# T_module.net
KiCad netlist of a schematic drawn in Altium Designer
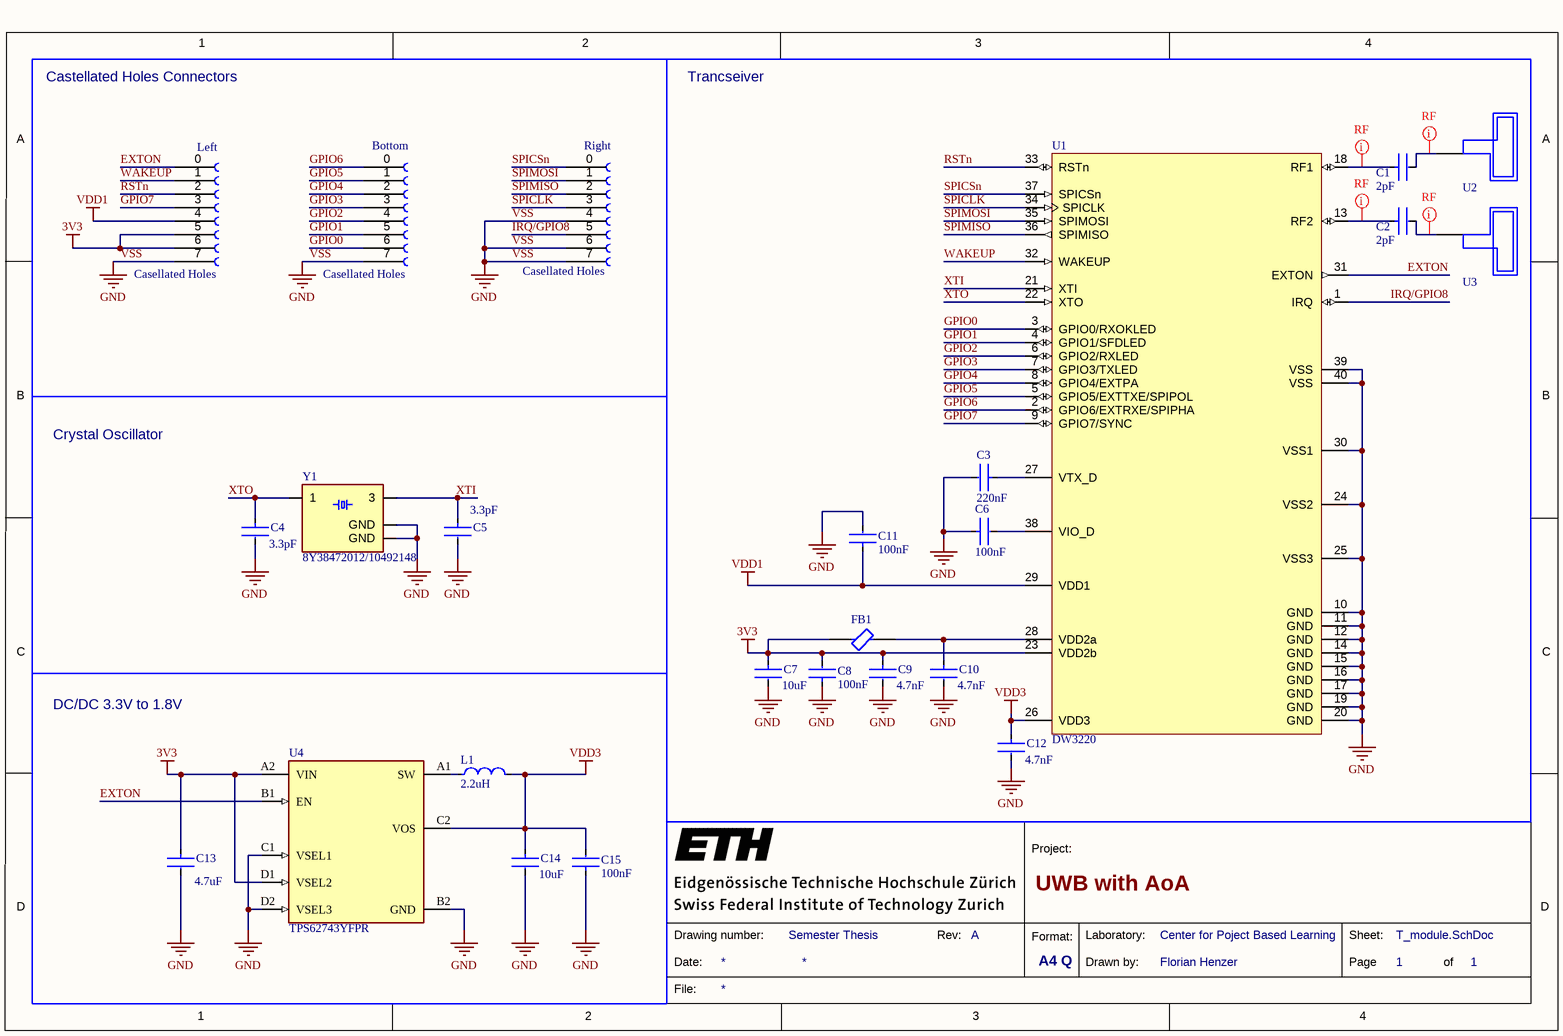
[diagram p0: T_module.SchDoc]

(export (version "E")
  (design (tool "Eeschema 10.0.6"))
  (components
    (comp (ref "Bottom")
      (value "Casellated Holes")
      (footprint "PcbLib1:8 Castelted holes")
      (libsource (lib "Schlib1") (part "Casellated Holes"))
    )
    (comp (ref "C1")
      (value "GJM0335C1E2R0WB01D")
      (footprint "FP-GJM033-0_03-IPC_B")
      (description "Ceramic Capacitor 2pF ±0.05pF 25V C0G 0201 (0603 Metric)")
      (fields (field (name "CAPACITANCE") "2pF"))
      (libsource (lib "Altium Content Vault") (part "b4654b650e69147ec39a6b967a45e02"))
    )
    (comp (ref "C2")
      (value "GJM0335C1E2R0WB01D")
      (footprint "FP-GJM033-0_03-IPC_B")
      (description "Ceramic Capacitor 2pF ±0.05pF 25V C0G 0201 (0603 Metric)")
      (fields (field (name "CAPACITANCE") "2pF"))
      (libsource (lib "Altium Content Vault") (part "b4654b650e69147ec39a6b967a45e02"))
    )
    (comp (ref "C3")
      (value "CL03A224KQ3NNNC")
      (footprint "FP-CL03-IPC_B")
      (description "Cap Ceramic 220nF 6.3V X5R ±10% Pad SMD 0201 +85°C T/R")
      (fields (field (name "CAPACITANCE") "220nF") (field (name "TOLERANCE") "10%"))
      (libsource (lib "Altium Content Vault") (part "b4654b650e69147ec39a6b967a45e02"))
    )
    (comp (ref "C4")
      (value "GRM0335C1H3R3CA01D")
      (footprint "FP-GRM033-0_03-IPC_A")
      (description "Chip Multilayer Ceramic Capacitors for General Purpose, 0201, 3.3pF, C0G, 30ppm/°C, 0.25pF, 50V")
      (fields (field (name "CAPACITANCE") "3.3pF"))
      (libsource (lib "Altium Content Vault") (part "b4654b650e69147ec39a6b967a45e02"))
    )
    (comp (ref "C5")
      (value "GRM0335C1H3R3CA01D")
      (footprint "FP-GRM033-0_03-IPC_A")
      (description "Chip Multilayer Ceramic Capacitors for General Purpose, 0201, 3.3pF, C0G, 30ppm/°C, 0.25pF, 50V")
      (fields (field (name "CAPACITANCE") "3.3pF"))
      (libsource (lib "Altium Content Vault") (part "b4654b650e69147ec39a6b967a45e02"))
    )
    (comp (ref "C6")
      (value "CL03A104KQ3NNNH")
      (footprint "FP-CL03-IPC_B")
      (description "Cap Ceramic 100nF 6.3V X5R ±10% Pad SMD 0201 +85°C T/R")
      (fields (field (name "TOLERANCE") "10%") (field (name "CAPACITANCE") "100nF"))
      (libsource (lib "Altium Content Vault") (part "b4654b650e69147ec39a6b967a45e02"))
    )
    (comp (ref "C7")
      (value "GRM155R60J106ME47D")
      (footprint "FP-GRM155-0_2-0_1-IPC_B")
      (description "Chip Multilayer Ceramic Capacitors for General Purpose, 0402, 10uF, X5R, 15%, 20%, 6.3V")
      (fields (field (name "TOLERANCE") "20%") (field (name "CAPACITANCE") "10uF"))
      (libsource (lib "Altium Content Vault") (part "b4654b650e69147ec39a6b967a45e02"))
    )
    (comp (ref "C8")
      (value "CL03A104KQ3NNNH")
      (footprint "FP-CL03-IPC_B")
      (description "Cap Ceramic 100nF 6.3V X5R ±10% Pad SMD 0201 +85°C T/R")
      (fields (field (name "TOLERANCE") "10%") (field (name "CAPACITANCE") "100nF"))
      (libsource (lib "Altium Content Vault") (part "b4654b650e69147ec39a6b967a45e02"))
    )
    (comp (ref "C9")
      (value "GRM033R71A472KA01D")
      (footprint "FP-GRM033-0_03-IPC_A")
      (description "Chip Multilayer Ceramic Capacitors for General Purpose, 0201, 4700pF, X7R, 15%, 10%, 10V")
      (fields
        (field (name "VOLTAGE") "10V")
        (field (name "CAPACITANCE") "4.7nF")
        (field (name "TOLERANCE") "10%")
      )
      (libsource (lib "Altium Content Vault") (part "b4654b650e69147ec39a6b967a45e02"))
    )
    (comp (ref "C10")
      (value "GRM033R71A472KA01D")
      (footprint "FP-GRM033-0_03-IPC_A")
      (description "Chip Multilayer Ceramic Capacitors for General Purpose, 0201, 4700pF, X7R, 15%, 10%, 10V")
      (fields
        (field (name "VOLTAGE") "10V")
        (field (name "CAPACITANCE") "4.7nF")
        (field (name "TOLERANCE") "10%")
      )
      (libsource (lib "Altium Content Vault") (part "b4654b650e69147ec39a6b967a45e02"))
    )
    (comp (ref "C11")
      (value "CL03A104KQ3NNNH")
      (footprint "FP-CL03-IPC_B")
      (description "Cap Ceramic 100nF 6.3V X5R ±10% Pad SMD 0201 +85°C T/R")
      (fields (field (name "TOLERANCE") "10%") (field (name "CAPACITANCE") "100nF"))
      (libsource (lib "Altium Content Vault") (part "b4654b650e69147ec39a6b967a45e02"))
    )
    (comp (ref "C12")
      (value "GRM033R71A472KA01D")
      (footprint "FP-GRM033-0_03-IPC_A")
      (description "Chip Multilayer Ceramic Capacitors for General Purpose, 0201, 4700pF, X7R, 15%, 10%, 10V")
      (fields
        (field (name "VOLTAGE") "10V")
        (field (name "CAPACITANCE") "4.7nF")
        (field (name "TOLERANCE") "10%")
      )
      (libsource (lib "Altium Content Vault") (part "b4654b650e69147ec39a6b967a45e02"))
    )
    (comp (ref "C13")
      (value "GRM035R60J475ME15D")
      (footprint "FP-GRM035-0_09-IPC_B")
      (description "Chip Multilayer Ceramic Capacitors for General Purpose, 0201, 4.7uF, X5R, 15%, 20%, 6.3V")
      (fields (field (name "CAPACITANCE") "4.7uF") (field (name "TOLERANCE") "20%"))
      (libsource (lib "Altium Content Vault") (part "02cd4be3c70576c341d710602a673aa"))
    )
    (comp (ref "C14")
      (value "GRM155R60J106ME47D")
      (footprint "FP-GRM155-0_2-0_1-IPC_C")
      (description "Chip Multilayer Ceramic Capacitors for General Purpose, 0402, 10uF, X5R, 15%, 20%, 6.3V")
      (fields (field (name "TOLERANCE") "20%") (field (name "CAPACITANCE") "10uF"))
      (libsource (lib "Altium Content Vault") (part "b4654b650e69147ec39a6b967a45e02"))
    )
    (comp (ref "C15")
      (value "CL03A104KQ3NNNH")
      (footprint "FP-CL03-IPC_B")
      (description "Cap Ceramic 100nF 6.3V X5R ±10% Pad SMD 0201 +85°C T/R")
      (fields (field (name "TOLERANCE") "10%") (field (name "CAPACITANCE") "100nF"))
      (libsource (lib "Altium Content Vault") (part "b4654b650e69147ec39a6b967a45e02"))
    )
    (comp (ref "FB1")
      (value "MPZ0603S330HT000")
      (footprint "FP-MPZ0603-IPC_B")
      (description "CHIP BEADS FOR GENERAL SIGNAL LI")
      (libsource (lib "Altium Content Vault") (part "5f30dd21d616792df468990f7003faa"))
    )
    (comp (ref "L1")
      (value "1285AS-H-2R2M=P2")
      (footprint "FP-DFE201610C-IPC_C")
      (description "Shielded Wirewound Inductor 2.2uH 20% 1200mA 0.204Ω 0806 (2016)")
      (fields (field (name "INDUCTANCE") "2.2uH") (field (name "TOLERANCE") "20%"))
      (libsource (lib "Altium Content Vault") (part "725321dda6339637d4d059423bc1c3c"))
    )
    (comp (ref "Left")
      (value "Casellated Holes")
      (footprint "PcbLib1:8 Castelted holes")
      (libsource (lib "Schlib1") (part "Casellated Holes"))
    )
    (comp (ref "Right")
      (value "Casellated Holes")
      (footprint "PcbLib1:8 Castelted holes")
      (libsource (lib "Schlib1") (part "Casellated Holes"))
    )
    (comp (ref "U1")
      (value "DW3220")
      (footprint "QFN40P500X500X40_HS-40N")
      (description "Ultra-low power Wi-Fi 802.11b/g/n, without mounted antenna")
      (fields (field (name "MANUFACTURER") "Qorvo"))
      (libsource (lib "ETHZ Vault") (part "DW3220"))
    )
    (comp (ref "U2")
      (value "AH086M555003-T")
      (footprint "AH086M")
      (description "3.5GHz, 5.6GHz WiMax™ Chip RF Antenna 3.1GHz ~ 8GHz 2.6dBi, 0.7dBi Solder Surface Mount")
      (libsource (lib "ETHZ Vault") (part "Antenna"))
    )
    (comp (ref "U3")
      (value "AH086M555003-T")
      (footprint "AH086M")
      (description "3.5GHz, 5.6GHz WiMax™ Chip RF Antenna 3.1GHz ~ 8GHz 2.6dBi, 0.7dBi Solder Surface Mount")
      (libsource (lib "ETHZ Vault") (part "Antenna"))
    )
    (comp (ref "U4")
      (value "TPS62743YFPR")
      (footprint "FP-YFP0008-C01-MFG")
      (description "IC REG BUCK PROG 300MA 8DSBGA")
      (libsource (lib "Altium Content Vault") (part "8afa53303d55f9e28cdff5b5725789a"))
    )
    (comp (ref "Y1")
      (value "8Y38472012/10492148")
      (footprint "OSCSC320X250X100N - small Footprint")
      (description "https://www.digikey.ch/de/products/detail/txc-corporation/8Y38472012/10492148")
      (libsource (lib "ABM8G-14.31818MHZ-B4Y-T") (part "ABM8G-14.31818MHZ-B4Y-T"))
    )
  )
  (nets
    (net (code "1") (name "/EXTON") (class "Default")
      (node (ref "Left") (pin "0") (pinfunction "0_0") (pintype "passive"))
      (node (ref "U1") (pin "31") (pinfunction "EXTON_31") (pintype "output"))
      (node (ref "U4") (pin "B1") (pinfunction "EN_B1") (pintype "input"))
    )
    (net (code "2") (name "/GPIO0") (class "Default")
      (node (ref "Bottom") (pin "6") (pinfunction "0_6") (pintype "passive"))
      (node (ref "U1") (pin "3") (pinfunction "GPIO0/RXOKLED_3") (pintype "bidirectional"))
    )
    (net (code "3") (name "/GPIO1") (class "Default")
      (node (ref "Bottom") (pin "5") (pinfunction "0_5") (pintype "passive"))
      (node (ref "U1") (pin "4") (pinfunction "GPIO1/SFDLED_4") (pintype "bidirectional"))
    )
    (net (code "4") (name "/GPIO2") (class "Default")
      (node (ref "Bottom") (pin "4") (pinfunction "0_4") (pintype "passive"))
      (node (ref "U1") (pin "6") (pinfunction "GPIO2/RXLED_6") (pintype "bidirectional"))
    )
    (net (code "5") (name "/GPIO3") (class "Default")
      (node (ref "Bottom") (pin "3") (pinfunction "0_3") (pintype "passive"))
      (node (ref "U1") (pin "7") (pinfunction "GPIO3/TXLED_7") (pintype "bidirectional"))
    )
    (net (code "6") (name "/GPIO4") (class "Default")
      (node (ref "Bottom") (pin "2") (pinfunction "0_2") (pintype "passive"))
      (node (ref "U1") (pin "8") (pinfunction "GPIO4/EXTPA_8") (pintype "bidirectional"))
    )
    (net (code "7") (name "/GPIO5") (class "Default")
      (node (ref "Bottom") (pin "1") (pinfunction "0_1") (pintype "passive"))
      (node (ref "U1") (pin "5") (pinfunction "GPIO5/EXTTXE/SPIPOL_5") (pintype "bidirectional"))
    )
    (net (code "8") (name "/GPIO6") (class "Default")
      (node (ref "Bottom") (pin "0") (pinfunction "0_0") (pintype "passive"))
      (node (ref "U1") (pin "2") (pinfunction "GPIO6/EXTRXE/SPIPHA_2") (pintype "bidirectional"))
    )
    (net (code "9") (name "/GPIO7") (class "Default")
      (node (ref "Left") (pin "3") (pinfunction "0_3") (pintype "passive"))
      (node (ref "U1") (pin "9") (pinfunction "GPIO7/SYNC_9") (pintype "bidirectional"))
    )
    (net (code "10") (name "/IRQ{slash}GPIO8") (class "Default")
      (node (ref "Right") (pin "5") (pinfunction "0_5") (pintype "passive"))
      (node (ref "U1") (pin "1") (pinfunction "IRQ_1") (pintype "bidirectional"))
    )
    (net (code "11") (name "/RSTn") (class "Default")
      (node (ref "Left") (pin "2") (pinfunction "0_2") (pintype "passive"))
      (node (ref "U1") (pin "33") (pinfunction "RSTn_33") (pintype "bidirectional"))
    )
    (net (code "12") (name "/SPICLK") (class "Default")
      (node (ref "Right") (pin "3") (pinfunction "0_3") (pintype "passive"))
      (node (ref "U1") (pin "34") (pinfunction "SPICLK_34") (pintype "input"))
    )
    (net (code "13") (name "/SPICSn") (class "Default")
      (node (ref "Right") (pin "0") (pinfunction "0_0") (pintype "passive"))
      (node (ref "U1") (pin "37") (pinfunction "SPICSn_37") (pintype "input"))
    )
    (net (code "14") (name "/SPIMISO") (class "Default")
      (node (ref "Right") (pin "2") (pinfunction "0_2") (pintype "passive"))
      (node (ref "U1") (pin "36") (pinfunction "SPIMISO_36") (pintype "output"))
    )
    (net (code "15") (name "/SPIMOSI") (class "Default")
      (node (ref "Right") (pin "1") (pinfunction "0_1") (pintype "passive"))
      (node (ref "U1") (pin "35") (pinfunction "SPIMOSI_35") (pintype "input"))
    )
    (net (code "16") (name "/WAKEUP") (class "Default")
      (node (ref "Left") (pin "1") (pinfunction "0_1") (pintype "passive"))
      (node (ref "U1") (pin "32") (pinfunction "WAKEUP_32") (pintype "input"))
    )
    (net (code "17") (name "/XTI") (class "Default")
      (node (ref "C5") (pin "1") (pinfunction "1_1") (pintype "passive"))
      (node (ref "U1") (pin "21") (pinfunction "XTI_21") (pintype "input"))
      (node (ref "Y1") (pin "3") (pinfunction "3_3") (pintype "passive"))
    )
    (net (code "18") (name "/XTO") (class "Default")
      (node (ref "C4") (pin "1") (pinfunction "1_1") (pintype "passive"))
      (node (ref "U1") (pin "22") (pinfunction "XTO_22") (pintype "input"))
      (node (ref "Y1") (pin "1") (pinfunction "1_1") (pintype "passive"))
    )
    (net (code "19") (name "3V3") (class "Default")
      (node (ref "C13") (pin "1") (pinfunction "1_1") (pintype "passive"))
      (node (ref "C7") (pin "1") (pinfunction "1_1") (pintype "passive"))
      (node (ref "C8") (pin "2") (pinfunction "2_2") (pintype "passive"))
      (node (ref "C9") (pin "1") (pinfunction "1_1") (pintype "passive"))
      (node (ref "FB1") (pin "1") (pinfunction "1_1") (pintype "passive"))
      (node (ref "Left") (pin "5") (pinfunction "0_5") (pintype "passive"))
      (node (ref "Left") (pin "6") (pinfunction "0_6") (pintype "passive"))
      (node (ref "U1") (pin "23") (pinfunction "VDD2b_23") (pintype "power_in"))
      (node (ref "U4") (pin "A2") (pinfunction "VIN_A2") (pintype "power_in"))
      (node (ref "U4") (pin "D1") (pinfunction "VSEL2_D1") (pintype "input"))
    )
    (net (code "20") (name "GND") (class "Default")
      (node (ref "Bottom") (pin "7") (pinfunction "0_7") (pintype "passive"))
      (node (ref "C10") (pin "2") (pinfunction "2_2") (pintype "passive"))
      (node (ref "C11") (pin "2") (pinfunction "2_2") (pintype "passive"))
      (node (ref "C12") (pin "2") (pinfunction "2_2") (pintype "passive"))
      (node (ref "C13") (pin "2") (pinfunction "2_2") (pintype "passive"))
      (node (ref "C14") (pin "2") (pinfunction "2_2") (pintype "passive"))
      (node (ref "C15") (pin "1") (pinfunction "1_1") (pintype "passive"))
      (node (ref "C3") (pin "2") (pinfunction "2_2") (pintype "passive"))
      (node (ref "C4") (pin "2") (pinfunction "2_2") (pintype "passive"))
      (node (ref "C5") (pin "2") (pinfunction "2_2") (pintype "passive"))
      (node (ref "C6") (pin "1") (pinfunction "1_1") (pintype "passive"))
      (node (ref "C7") (pin "2") (pinfunction "2_2") (pintype "passive"))
      (node (ref "C8") (pin "1") (pinfunction "1_1") (pintype "passive"))
      (node (ref "C9") (pin "2") (pinfunction "2_2") (pintype "passive"))
      (node (ref "Left") (pin "7") (pinfunction "0_7") (pintype "passive"))
      (node (ref "Right") (pin "4") (pinfunction "0_4") (pintype "passive"))
      (node (ref "Right") (pin "6") (pinfunction "0_6") (pintype "passive"))
      (node (ref "Right") (pin "7") (pinfunction "0_7") (pintype "passive"))
      (node (ref "U1") (pin "10") (pinfunction "GND_10") (pintype "power_in"))
      (node (ref "U1") (pin "11") (pinfunction "GND_11") (pintype "power_in"))
      (node (ref "U1") (pin "12") (pinfunction "GND_12") (pintype "power_in"))
      (node (ref "U1") (pin "14") (pinfunction "GND_14") (pintype "power_in"))
      (node (ref "U1") (pin "15") (pinfunction "GND_15") (pintype "power_in"))
      (node (ref "U1") (pin "16") (pinfunction "GND_16") (pintype "power_in"))
      (node (ref "U1") (pin "17") (pinfunction "GND_17") (pintype "power_in"))
      (node (ref "U1") (pin "19") (pinfunction "GND_19") (pintype "power_in"))
      (node (ref "U1") (pin "20") (pinfunction "GND_20") (pintype "power_in"))
      (node (ref "U1") (pin "24") (pinfunction "VSS2_24") (pintype "power_in"))
      (node (ref "U1") (pin "25") (pinfunction "VSS3_25") (pintype "power_in"))
      (node (ref "U1") (pin "30") (pinfunction "VSS1_30") (pintype "power_in"))
      (node (ref "U1") (pin "39") (pinfunction "VSS_39") (pintype "power_in"))
      (node (ref "U1") (pin "40") (pinfunction "VSS_40") (pintype "power_in"))
      (node (ref "U4") (pin "B2") (pinfunction "GND_B2") (pintype "power_in"))
      (node (ref "U4") (pin "C1") (pinfunction "VSEL1_C1") (pintype "input"))
      (node (ref "U4") (pin "D2") (pinfunction "VSEL3_D2") (pintype "input"))
      (node (ref "Y1") (pin "2") (pinfunction "GND_2") (pintype "power_in"))
      (node (ref "Y1") (pin "4") (pinfunction "GND_4") (pintype "power_in"))
    )
    (net (code "21") (name "Net-(C1-Pad2)") (class "Default")
      (node (ref "C1") (pin "2") (pinfunction "2_2") (pintype "passive"))
      (node (ref "U2") (pin "1") (pinfunction "1_1") (pintype "passive"))
    )
    (net (code "22") (name "Net-(C2-Pad2)") (class "Default")
      (node (ref "C2") (pin "2") (pinfunction "2_2") (pintype "passive"))
      (node (ref "U3") (pin "1") (pinfunction "1_1") (pintype "passive"))
    )
    (net (code "23") (name "Net-(U1-RF1)") (class "Default")
      (node (ref "C1") (pin "1") (pinfunction "1_1") (pintype "passive"))
      (node (ref "U1") (pin "18") (pinfunction "RF1_18") (pintype "bidirectional"))
    )
    (net (code "24") (name "Net-(U1-RF2)") (class "Default")
      (node (ref "C2") (pin "1") (pinfunction "1_1") (pintype "passive"))
      (node (ref "U1") (pin "13") (pinfunction "RF2_13") (pintype "bidirectional"))
    )
    (net (code "25") (name "Net-(U1-VDD2a)") (class "Default")
      (node (ref "C10") (pin "1") (pinfunction "1_1") (pintype "passive"))
      (node (ref "FB1") (pin "2") (pinfunction "2_2") (pintype "passive"))
      (node (ref "U1") (pin "28") (pinfunction "VDD2a_28") (pintype "power_in"))
    )
    (net (code "26") (name "Net-(U1-VIO_D)") (class "Default")
      (node (ref "C6") (pin "2") (pinfunction "2_2") (pintype "passive"))
      (node (ref "U1") (pin "38") (pinfunction "VIO_D_38") (pintype "passive"))
    )
    (net (code "27") (name "Net-(U1-VTX_D)") (class "Default")
      (node (ref "C3") (pin "1") (pinfunction "1_1") (pintype "passive"))
      (node (ref "U1") (pin "27") (pinfunction "VTX_D_27") (pintype "passive"))
    )
    (net (code "28") (name "Net-(U4-SW)") (class "Default")
      (node (ref "L1") (pin "1") (pinfunction "1_1") (pintype "passive"))
      (node (ref "U4") (pin "A1") (pinfunction "SW_A1") (pintype "passive"))
    )
    (net (code "29") (name "VDD1") (class "Default")
      (node (ref "C11") (pin "1") (pinfunction "1_1") (pintype "passive"))
      (node (ref "Left") (pin "4") (pinfunction "0_4") (pintype "passive"))
      (node (ref "U1") (pin "29") (pinfunction "VDD1_29") (pintype "power_in"))
    )
    (net (code "30") (name "VDD3") (class "Default")
      (node (ref "C12") (pin "1") (pinfunction "1_1") (pintype "passive"))
      (node (ref "C14") (pin "1") (pinfunction "1_1") (pintype "passive"))
      (node (ref "C15") (pin "2") (pinfunction "2_2") (pintype "passive"))
      (node (ref "L1") (pin "2") (pinfunction "2_2") (pintype "passive"))
      (node (ref "U1") (pin "26") (pinfunction "VDD3_26") (pintype "power_in"))
      (node (ref "U4") (pin "C2") (pinfunction "VOS_C2") (pintype "passive"))
    )
  )
)
